# PowerSubsystem.net
KiCad netlist of a schematic drawn in Altium Designer
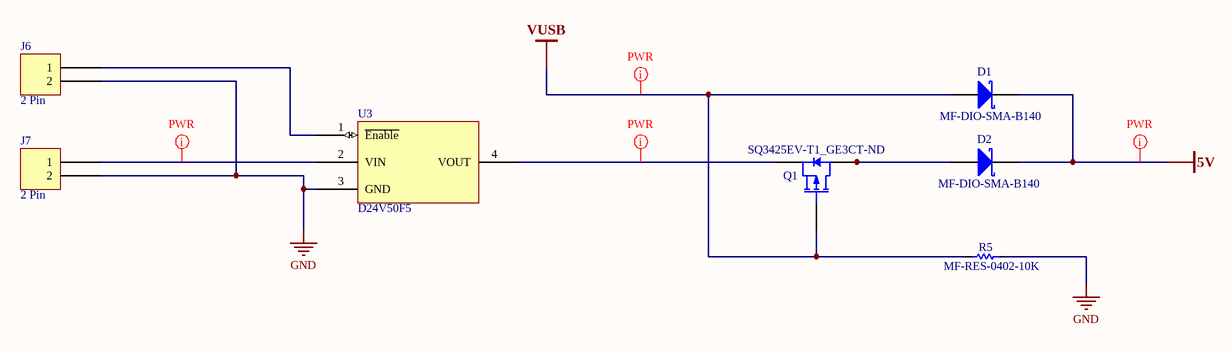
[diagram p0: PowerSubsystem.SchDoc]

(export (version "E")
  (design (tool "Eeschema 10.0.6"))
  (components
    (comp (ref "D1")
      (value "MF-DIO-SMA-B140")
      (footprint "Diode SMA")
      (fields (field (name "HOUSEPART") "YES") (field (name "MPN") "B140-13-F"))
      (libsource (lib "DiscreetSemiconductors") (part "Schottky Diode"))
    )
    (comp (ref "D2")
      (value "MF-DIO-SMA-B140")
      (footprint "Diode SMA")
      (fields (field (name "HOUSEPART") "YES") (field (name "MPN") "B140-13-F"))
      (libsource (lib "DiscreetSemiconductors") (part "Schottky Diode"))
    )
    (comp (ref "J6") (value "2 Pin") (footprint "Pinhead_1x2") (libsource (lib "Connectors") (part "2 Pin")))
    (comp (ref "J7") (value "2 Pin") (footprint "Pinhead_1x2") (libsource (lib "Connectors") (part "2 Pin")))
    (comp (ref "Q1")
      (value "MOSFET P-CH SOT26 / SOP-6")
      (footprint "TSOP-6_L")
      (fields
        (field (name "MF_PARTNUM") "SQ3425EV-T1_GE3CT-ND")
        (field (name "HOUSEPART") "NO")
        (field (name "MPN") "SQ3425EV")
        (field (name "SUPPLIER PART NUMBER 1") "SQ3425EV-T1_GE3CT-ND")
      )
      (libsource (lib "DiscreetSemiconductors") (part "MOSFET P-CH SOT26 / SOP-6"))
    )
    (comp (ref "R5")
      (value "MF-RES-0402-10K")
      (footprint "R0402L")
      (fields
        (field (name "HOUSEPART") "YES")
        (field (name "TOLERANCE") "5%")
        (field (name "VOLTAGE") "50 V")
      )
      (libsource (lib "MF_Passives") (part "RESISTOR"))
    )
    (comp (ref "U3")
      (value "D24V50F5")
      (footprint "D24V50Fx")
      (description "DC Step Down Regulators from Pololu")
      (libsource (lib "BreakoutBoards") (part "D24V25Fx"))
    )
  )
  (nets
    (net (code "1") (name "5V") (class "Default")
      (node (ref "D1") (pin "1") (pinfunction "K_1") (pintype "passive"))
      (node (ref "D2") (pin "1") (pinfunction "K_1") (pintype "passive"))
    )
    (net (code "2") (name "GND") (class "Default")
      (node (ref "J6") (pin "2") (pinfunction "2_2") (pintype "passive"))
      (node (ref "J7") (pin "2") (pinfunction "2_2") (pintype "passive"))
      (node (ref "R5") (pin "2") (pinfunction "2_2") (pintype "passive"))
      (node (ref "U3") (pin "3") (pinfunction "GND_3") (pintype "power_in"))
    )
    (net (code "3") (name "Net-(D2-A)") (class "Default")
      (node (ref "D2") (pin "2") (pinfunction "A_2") (pintype "passive"))
      (node (ref "Q1") (pin "1") (pinfunction "D_1") (pintype "passive"))
      (node (ref "Q1") (pin "2") (pinfunction "D_2") (pintype "passive"))
      (node (ref "Q1") (pin "5") (pinfunction "D_5") (pintype "passive"))
      (node (ref "Q1") (pin "6") (pinfunction "D_6") (pintype "passive"))
    )
    (net (code "4") (name "Net-(Q1-S)") (class "Default")
      (node (ref "Q1") (pin "4") (pinfunction "S_4") (pintype "passive"))
      (node (ref "U3") (pin "4") (pinfunction "VOUT_4") (pintype "power_in"))
    )
    (net (code "5") (name "Net-(U3-VIN)") (class "Default")
      (node (ref "J7") (pin "1") (pinfunction "1_1") (pintype "passive"))
      (node (ref "U3") (pin "2") (pinfunction "VIN_2") (pintype "power_in"))
    )
    (net (code "6") (name "Net-(U3-~{Enable})") (class "Default")
      (node (ref "J6") (pin "1") (pinfunction "1_1") (pintype "passive"))
      (node (ref "U3") (pin "1") (pinfunction "~{Enable}_1") (pintype "bidirectional"))
    )
    (net (code "7") (name "VUSB") (class "Default")
      (node (ref "D1") (pin "2") (pinfunction "A_2") (pintype "passive"))
      (node (ref "Q1") (pin "3") (pinfunction "G_3") (pintype "passive"))
      (node (ref "R5") (pin "1") (pinfunction "1_1") (pintype "passive"))
    )
  )
)
